# Debugger_1.net
KiCad netlist of a schematic drawn in EAGLE
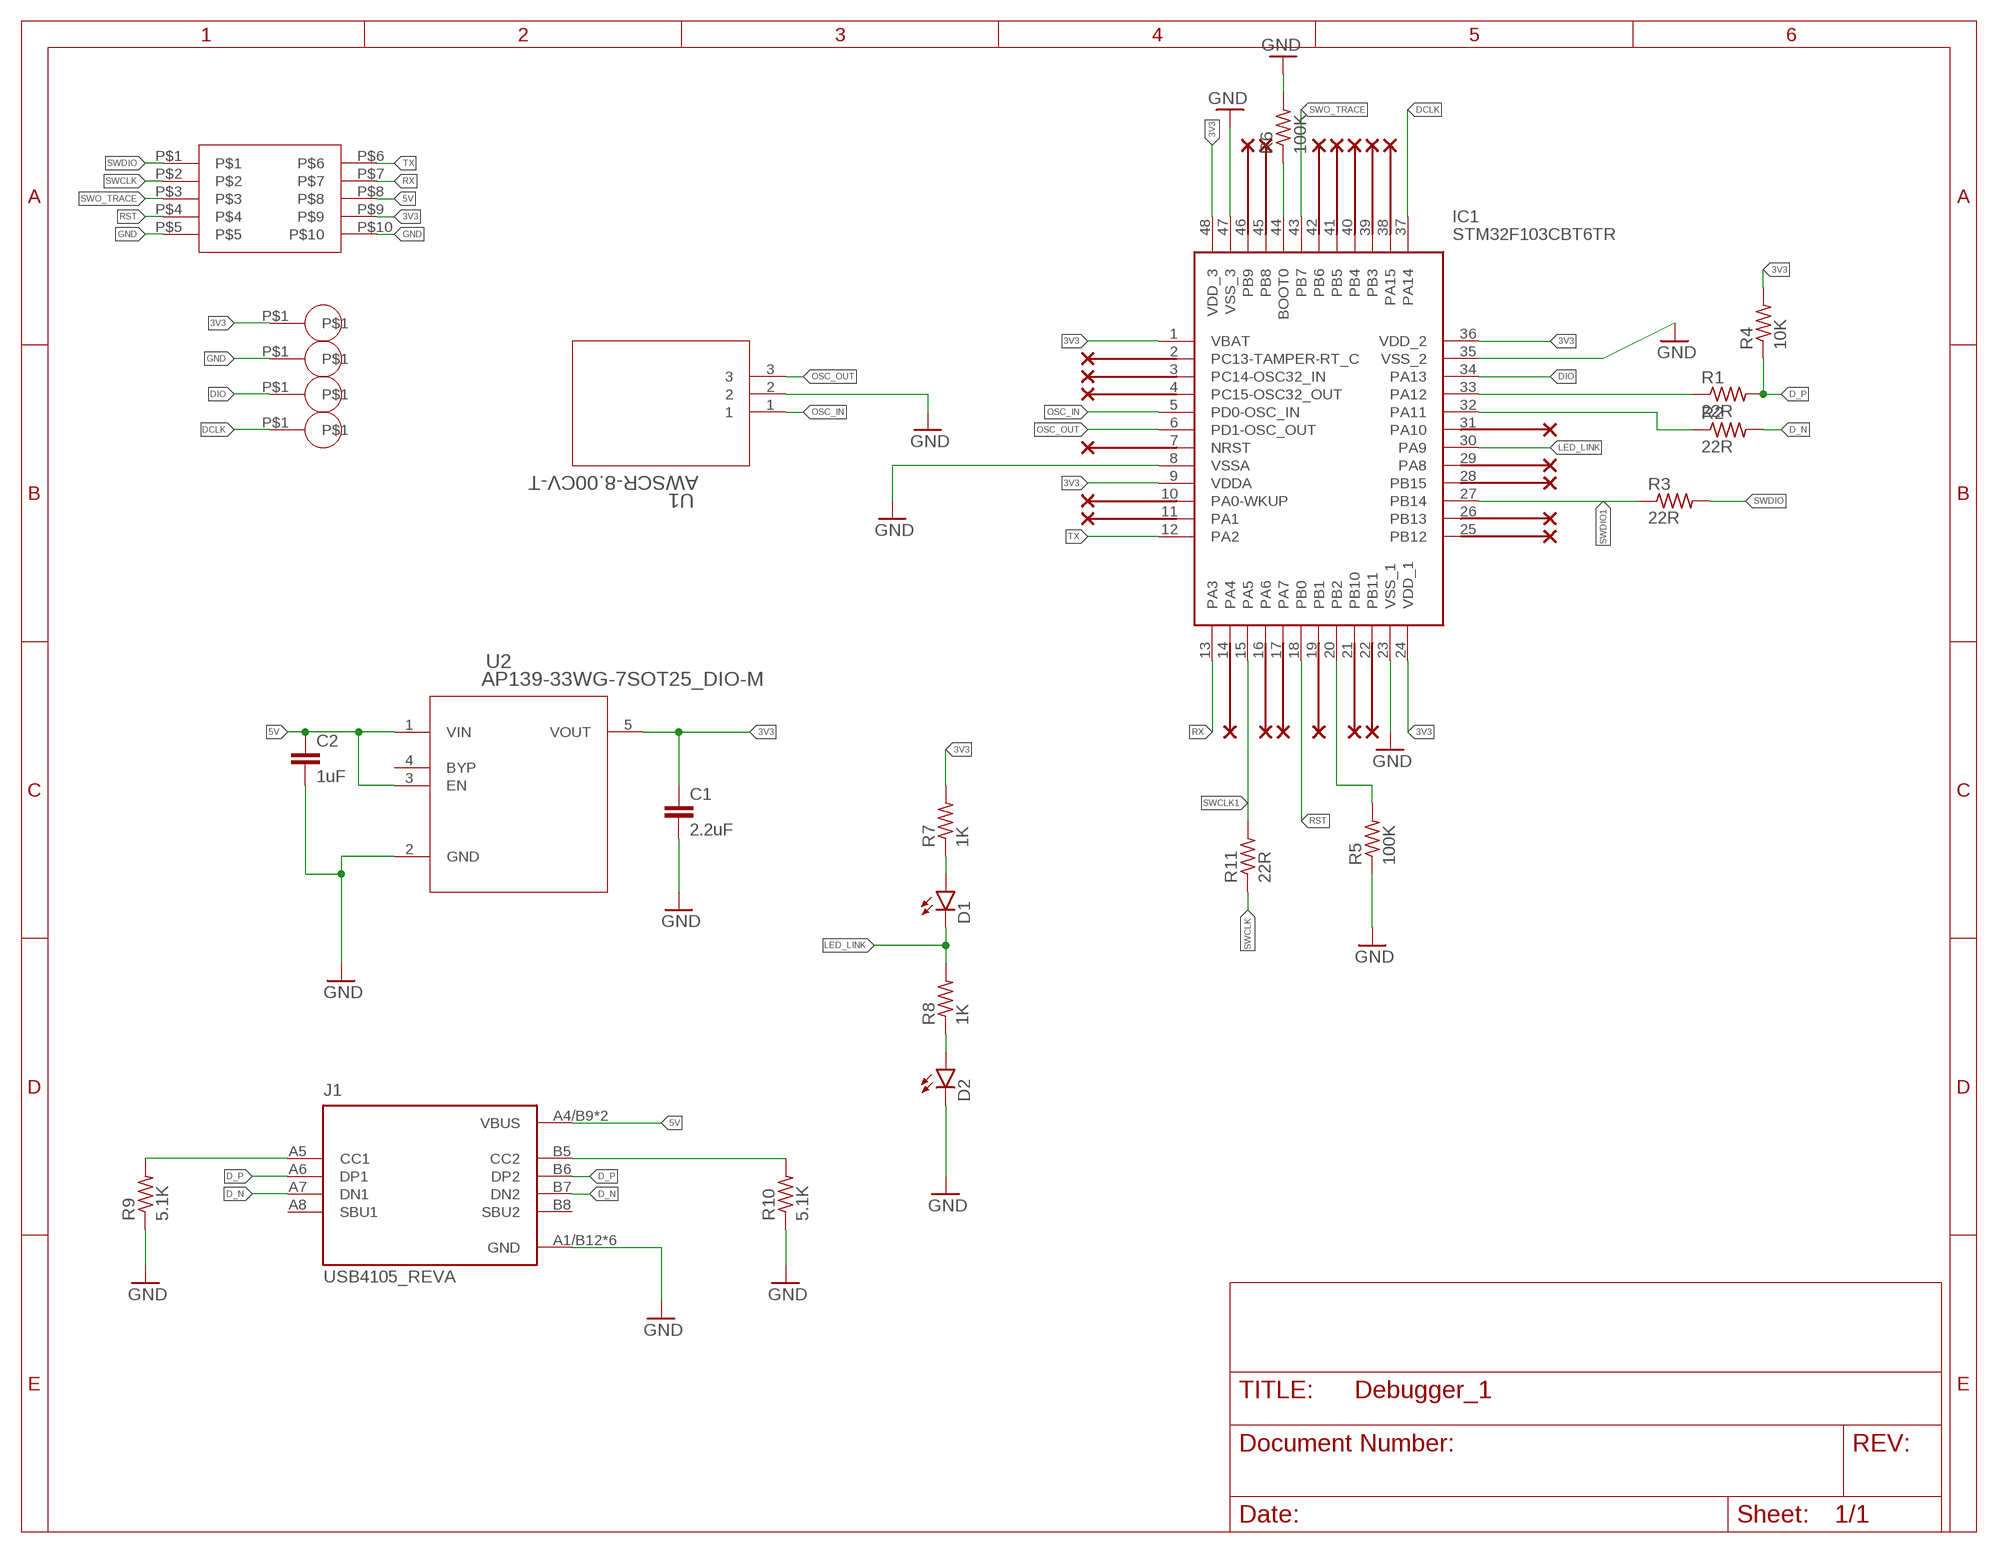
[diagram p0: schematic, sheet 1]

(export (version "E")
  (design (tool "Eeschema 10.0.6"))
  (components
    (comp (ref "C1")
      (value "2.2uF")
      (footprint "eagle-import:C0603")
      (libsource (lib "eagle-import") (part "C-EUC0603"))
    )
    (comp (ref "C2")
      (value "1uF")
      (footprint "eagle-import:C0603")
      (libsource (lib "eagle-import") (part "C-EUC0603"))
    )
    (comp (ref "D1")
      (value "LEDCHIPLED_0603")
      (footprint "eagle-import:CHIPLED_0603")
      (libsource (lib "eagle-import") (part "LEDCHIPLED_0603"))
    )
    (comp (ref "D2")
      (value "LEDCHIPLED_0603")
      (footprint "eagle-import:CHIPLED_0603")
      (libsource (lib "eagle-import") (part "LEDCHIPLED_0603"))
    )
    (comp (ref "IC1")
      (value "STM32F103CBT6TR")
      (footprint "eagle-import:QFP50P900X900X160-48N")
      (fields (field (name "MOUSER_PART_NUMBER") "511-STM32F103CBT6TR"))
      (libsource (lib "eagle-import") (part "STM32F103CBT6TR"))
    )
    (comp (ref "J1")
      (value "USB4105_REVA")
      (footprint "eagle-import:GCT_USB4105_REVA")
      (fields (field (name "MF") "Global Connector Technology") (field (name "MP") "USB4105"))
      (libsource (lib "eagle-import") (part "USB4105_REVA"))
    )
    (comp (ref "R1")
      (value "22R")
      (footprint "eagle-import:R0603")
      (libsource (lib "eagle-import") (part "R-US_R0603"))
    )
    (comp (ref "R2")
      (value "22R")
      (footprint "eagle-import:R0603")
      (libsource (lib "eagle-import") (part "R-US_R0603"))
    )
    (comp (ref "R3")
      (value "22R")
      (footprint "eagle-import:R0603")
      (libsource (lib "eagle-import") (part "R-US_R0603"))
    )
    (comp (ref "R4")
      (value "10K")
      (footprint "eagle-import:R0603")
      (libsource (lib "eagle-import") (part "R-US_R0603"))
    )
    (comp (ref "R5")
      (value "100K")
      (footprint "eagle-import:R0603")
      (libsource (lib "eagle-import") (part "R-US_R0603"))
    )
    (comp (ref "R6")
      (value "100K")
      (footprint "eagle-import:R0603")
      (libsource (lib "eagle-import") (part "R-US_R0603"))
    )
    (comp (ref "R7")
      (value "1K")
      (footprint "eagle-import:R0603")
      (libsource (lib "eagle-import") (part "R-US_R0603"))
    )
    (comp (ref "R8")
      (value "1K")
      (footprint "eagle-import:R0603")
      (libsource (lib "eagle-import") (part "R-US_R0603"))
    )
    (comp (ref "R9")
      (value "5.1K")
      (footprint "eagle-import:R0603")
      (libsource (lib "eagle-import") (part "R-US_R0603"))
    )
    (comp (ref "R10")
      (value "5.1K")
      (footprint "eagle-import:R0603")
      (libsource (lib "eagle-import") (part "R-US_R0603"))
    )
    (comp (ref "R11")
      (value "22R")
      (footprint "eagle-import:R0603")
      (libsource (lib "eagle-import") (part "R-US_R0603"))
    )
    (comp (ref "U$25")
      (value "SIDEWAYS_HEADER_10")
      (footprint "eagle-import:SIDEWAYS_HEADER_10")
      (libsource (lib "eagle-import") (part "SIDEWAYS_HEADER_10"))
    )
    (comp (ref "U$26")
      (value "SPRING_PAD_1")
      (footprint "eagle-import:SPRING_PAD_1")
      (libsource (lib "eagle-import") (part "SPRING_PAD_1"))
    )
    (comp (ref "U$27")
      (value "SPRING_PAD_1")
      (footprint "eagle-import:SPRING_PAD_1")
      (libsource (lib "eagle-import") (part "SPRING_PAD_1"))
    )
    (comp (ref "U$28")
      (value "SPRING_PAD_1")
      (footprint "eagle-import:SPRING_PAD_1")
      (libsource (lib "eagle-import") (part "SPRING_PAD_1"))
    )
    (comp (ref "U$29")
      (value "SPRING_PAD_1")
      (footprint "eagle-import:SPRING_PAD_1")
      (libsource (lib "eagle-import") (part "SPRING_PAD_1"))
    )
    (comp (ref "U1")
      (value "AWSCR-8.00CV-T")
      (footprint "eagle-import:AWSCR-8.00CV-T_ABR")
      (fields (field (name "COPYRIGHT") "Copyright (C) 2021 Ultra Librarian. All rights reserved."))
      (libsource (lib "eagle-import") (part "AWSCR-8.00CV-T"))
    )
    (comp (ref "U2")
      (value "AP139-33WG-7SOT25_DIO-M")
      (footprint "eagle-import:SOT25_DIO-M")
      (fields
        (field (name "MANUFACTURER_PART_NUMBER") "AP139-33WG-7")
        (field (name "COPYRIGHT") "Copyright (C) 2021 Ultra Librarian. All rights reserved.")
      )
      (libsource (lib "eagle-import") (part "AP139-33WG-7SOT25_DIO-M"))
    )
  )
  (nets
    (net (code "1") (name "3V3") (class "Default")
      (node (ref "C1") (pin "1") (pinfunction "1_1") (pintype "passive"))
      (node (ref "IC1") (pin "1") (pinfunction "VBAT_1") (pintype "bidirectional"))
      (node (ref "IC1") (pin "24") (pinfunction "VDD_1_24") (pintype "bidirectional"))
      (node (ref "IC1") (pin "36") (pinfunction "VDD_2_36") (pintype "bidirectional"))
      (node (ref "IC1") (pin "48") (pinfunction "VDD_3_48") (pintype "bidirectional"))
      (node (ref "IC1") (pin "9") (pinfunction "VDDA_9") (pintype "bidirectional"))
      (node (ref "R4") (pin "2") (pinfunction "2_2") (pintype "passive"))
      (node (ref "R7") (pin "2") (pinfunction "2_2") (pintype "passive"))
      (node (ref "U$25") (pin "P$9") (pinfunction "P$9_P$9") (pintype "bidirectional"))
      (node (ref "U$26") (pin "P$1") (pinfunction "P$1_P$1") (pintype "bidirectional"))
      (node (ref "U2") (pin "5") (pinfunction "VOUT_5") (pintype "output"))
    )
    (net (code "2") (name "5V") (class "Default")
      (node (ref "C2") (pin "1") (pinfunction "1_1") (pintype "passive"))
      (node (ref "J1") (pin "A4/B9") (pinfunction "VBUS_A4/B9") (pintype "power_in"))
      (node (ref "J1") (pin "B4/A9") (pinfunction "VBUS_B4/A9") (pintype "power_in"))
      (node (ref "U$25") (pin "P$8") (pinfunction "P$8_P$8") (pintype "bidirectional"))
      (node (ref "U2") (pin "1") (pinfunction "VIN_1") (pintype "input"))
      (node (ref "U2") (pin "3") (pinfunction "EN_3") (pintype "passive"))
    )
    (net (code "3") (name "DCLK") (class "Default")
      (node (ref "IC1") (pin "37") (pinfunction "PA14_37") (pintype "bidirectional"))
      (node (ref "U$29") (pin "P$1") (pinfunction "P$1_P$1") (pintype "bidirectional"))
    )
    (net (code "4") (name "DIO") (class "Default")
      (node (ref "IC1") (pin "34") (pinfunction "PA13_34") (pintype "bidirectional"))
      (node (ref "U$28") (pin "P$1") (pinfunction "P$1_P$1") (pintype "bidirectional"))
    )
    (net (code "5") (name "D_N") (class "Default")
      (node (ref "J1") (pin "A7") (pinfunction "DN1_A7") (pintype "bidirectional"))
      (node (ref "J1") (pin "B7") (pinfunction "DN2_B7") (pintype "bidirectional"))
      (node (ref "R2") (pin "2") (pinfunction "2_2") (pintype "passive"))
    )
    (net (code "6") (name "D_P") (class "Default")
      (node (ref "J1") (pin "A6") (pinfunction "DP1_A6") (pintype "bidirectional"))
      (node (ref "J1") (pin "B6") (pinfunction "DP2_B6") (pintype "bidirectional"))
      (node (ref "R1") (pin "2") (pinfunction "2_2") (pintype "passive"))
      (node (ref "R4") (pin "1") (pinfunction "1_1") (pintype "passive"))
    )
    (net (code "7") (name "GND") (class "Default")
      (node (ref "C1") (pin "2") (pinfunction "2_2") (pintype "passive"))
      (node (ref "C2") (pin "2") (pinfunction "2_2") (pintype "passive"))
      (node (ref "D2") (pin "C") (pinfunction "C_C") (pintype "passive"))
      (node (ref "IC1") (pin "23") (pinfunction "VSS_1_23") (pintype "bidirectional"))
      (node (ref "IC1") (pin "35") (pinfunction "VSS_2_35") (pintype "bidirectional"))
      (node (ref "IC1") (pin "47") (pinfunction "VSS_3_47") (pintype "bidirectional"))
      (node (ref "IC1") (pin "8") (pinfunction "VSSA_8") (pintype "bidirectional"))
      (node (ref "J1") (pin "A1/B12") (pinfunction "GND_A1/B12") (pintype "power_in"))
      (node (ref "J1") (pin "B1/A12") (pinfunction "GND_B1/A12") (pintype "power_in"))
      (node (ref "J1") (pin "G1") (pinfunction "GND_G1") (pintype "power_in"))
      (node (ref "J1") (pin "G2") (pinfunction "GND_G2") (pintype "power_in"))
      (node (ref "J1") (pin "G3") (pinfunction "GND_G3") (pintype "power_in"))
      (node (ref "J1") (pin "G4") (pinfunction "GND_G4") (pintype "power_in"))
      (node (ref "R10") (pin "1") (pinfunction "1_1") (pintype "passive"))
      (node (ref "R5") (pin "1") (pinfunction "1_1") (pintype "passive"))
      (node (ref "R6") (pin "2") (pinfunction "2_2") (pintype "passive"))
      (node (ref "R9") (pin "1") (pinfunction "1_1") (pintype "passive"))
      (node (ref "U$25") (pin "P$10") (pinfunction "P$10_P$10") (pintype "bidirectional"))
      (node (ref "U$25") (pin "P$5") (pinfunction "P$5_P$5") (pintype "bidirectional"))
      (node (ref "U$27") (pin "P$1") (pinfunction "P$1_P$1") (pintype "bidirectional"))
      (node (ref "U1") (pin "2") (pinfunction "2_2") (pintype "passive"))
      (node (ref "U2") (pin "2") (pinfunction "GND_2") (pintype "power_in"))
    )
    (net (code "8") (name "LED_LINK") (class "Default")
      (node (ref "D1") (pin "C") (pinfunction "C_C") (pintype "passive"))
      (node (ref "IC1") (pin "30") (pinfunction "PA9_30") (pintype "bidirectional"))
      (node (ref "R8") (pin "2") (pinfunction "2_2") (pintype "passive"))
    )
    (net (code "9") (name "Net-(D1-PadA)") (class "Default")
      (node (ref "D1") (pin "A") (pinfunction "A_A") (pintype "passive"))
      (node (ref "R7") (pin "1") (pinfunction "1_1") (pintype "passive"))
    )
    (net (code "10") (name "Net-(D2-PadA)") (class "Default")
      (node (ref "D2") (pin "A") (pinfunction "A_A") (pintype "passive"))
      (node (ref "R8") (pin "1") (pinfunction "1_1") (pintype "passive"))
    )
    (net (code "11") (name "Net-(IC1-BOOT0)") (class "Default")
      (node (ref "IC1") (pin "44") (pinfunction "BOOT0_44") (pintype "bidirectional"))
      (node (ref "R6") (pin "1") (pinfunction "1_1") (pintype "passive"))
    )
    (net (code "12") (name "Net-(IC1-PA11)") (class "Default")
      (node (ref "IC1") (pin "32") (pinfunction "PA11_32") (pintype "bidirectional"))
      (node (ref "R2") (pin "1") (pinfunction "1_1") (pintype "passive"))
    )
    (net (code "13") (name "Net-(IC1-PA12)") (class "Default")
      (node (ref "IC1") (pin "33") (pinfunction "PA12_33") (pintype "bidirectional"))
      (node (ref "R1") (pin "1") (pinfunction "1_1") (pintype "passive"))
    )
    (net (code "14") (name "Net-(IC1-PB2)") (class "Default")
      (node (ref "IC1") (pin "20") (pinfunction "PB2_20") (pintype "bidirectional"))
      (node (ref "R5") (pin "2") (pinfunction "2_2") (pintype "passive"))
    )
    (net (code "15") (name "Net-(J1-CC1)") (class "Default")
      (node (ref "J1") (pin "A5") (pinfunction "CC1_A5") (pintype "bidirectional"))
      (node (ref "R9") (pin "2") (pinfunction "2_2") (pintype "passive"))
    )
    (net (code "16") (name "Net-(J1-CC2)") (class "Default")
      (node (ref "J1") (pin "B5") (pinfunction "CC2_B5") (pintype "bidirectional"))
      (node (ref "R10") (pin "2") (pinfunction "2_2") (pintype "passive"))
    )
    (net (code "17") (name "OSC_IN") (class "Default")
      (node (ref "IC1") (pin "5") (pinfunction "PD0-OSC_IN_5") (pintype "bidirectional"))
      (node (ref "U1") (pin "1") (pinfunction "1_1") (pintype "passive"))
    )
    (net (code "18") (name "OSC_OUT") (class "Default")
      (node (ref "IC1") (pin "6") (pinfunction "PD1-OSC_OUT_6") (pintype "bidirectional"))
      (node (ref "U1") (pin "3") (pinfunction "3_3") (pintype "passive"))
    )
    (net (code "19") (name "RST") (class "Default")
      (node (ref "IC1") (pin "18") (pinfunction "PB0_18") (pintype "bidirectional"))
      (node (ref "U$25") (pin "P$4") (pinfunction "P$4_P$4") (pintype "bidirectional"))
    )
    (net (code "20") (name "RX") (class "Default")
      (node (ref "IC1") (pin "13") (pinfunction "PA3_13") (pintype "bidirectional"))
      (node (ref "U$25") (pin "P$7") (pinfunction "P$7_P$7") (pintype "bidirectional"))
    )
    (net (code "21") (name "SWCLK") (class "Default")
      (node (ref "R11") (pin "1") (pinfunction "1_1") (pintype "passive"))
      (node (ref "U$25") (pin "P$2") (pinfunction "P$2_P$2") (pintype "bidirectional"))
    )
    (net (code "22") (name "SWCLK1") (class "Default")
      (node (ref "IC1") (pin "15") (pinfunction "PA5_15") (pintype "bidirectional"))
      (node (ref "R11") (pin "2") (pinfunction "2_2") (pintype "passive"))
    )
    (net (code "23") (name "SWDIO") (class "Default")
      (node (ref "R3") (pin "2") (pinfunction "2_2") (pintype "passive"))
      (node (ref "U$25") (pin "P$1") (pinfunction "P$1_P$1") (pintype "bidirectional"))
    )
    (net (code "24") (name "SWDIO1") (class "Default")
      (node (ref "IC1") (pin "27") (pinfunction "PB14_27") (pintype "bidirectional"))
      (node (ref "R3") (pin "1") (pinfunction "1_1") (pintype "passive"))
    )
    (net (code "25") (name "SWO_TRACE") (class "Default")
      (node (ref "IC1") (pin "43") (pinfunction "PB7_43") (pintype "bidirectional"))
      (node (ref "U$25") (pin "P$3") (pinfunction "P$3_P$3") (pintype "bidirectional"))
    )
    (net (code "26") (name "TX") (class "Default")
      (node (ref "IC1") (pin "12") (pinfunction "PA2_12") (pintype "bidirectional"))
      (node (ref "U$25") (pin "P$6") (pinfunction "P$6_P$6") (pintype "bidirectional"))
    )
    (net (code "27") (name "unconnected-(IC1-NRST-Pad7)") (class "Default")
      (node (ref "IC1") (pin "7") (pinfunction "NRST_7") (pintype "bidirectional"))
    )
    (net (code "28") (name "unconnected-(IC1-PA0-WKUP-Pad10)") (class "Default")
      (node (ref "IC1") (pin "10") (pinfunction "PA0-WKUP_10") (pintype "bidirectional"))
    )
    (net (code "29") (name "unconnected-(IC1-PA1-Pad11)") (class "Default")
      (node (ref "IC1") (pin "11") (pinfunction "PA1_11") (pintype "bidirectional"))
    )
    (net (code "30") (name "unconnected-(IC1-PA4-Pad14)") (class "Default")
      (node (ref "IC1") (pin "14") (pinfunction "PA4_14") (pintype "bidirectional"))
    )
    (net (code "31") (name "unconnected-(IC1-PA6-Pad16)") (class "Default")
      (node (ref "IC1") (pin "16") (pinfunction "PA6_16") (pintype "bidirectional"))
    )
    (net (code "32") (name "unconnected-(IC1-PA7-Pad17)") (class "Default")
      (node (ref "IC1") (pin "17") (pinfunction "PA7_17") (pintype "bidirectional"))
    )
    (net (code "33") (name "unconnected-(IC1-PA8-Pad29)") (class "Default")
      (node (ref "IC1") (pin "29") (pinfunction "PA8_29") (pintype "bidirectional"))
    )
    (net (code "34") (name "unconnected-(IC1-PA10-Pad31)") (class "Default")
      (node (ref "IC1") (pin "31") (pinfunction "PA10_31") (pintype "bidirectional"))
    )
    (net (code "35") (name "unconnected-(IC1-PA15-Pad38)") (class "Default")
      (node (ref "IC1") (pin "38") (pinfunction "PA15_38") (pintype "bidirectional"))
    )
    (net (code "36") (name "unconnected-(IC1-PB1-Pad19)") (class "Default")
      (node (ref "IC1") (pin "19") (pinfunction "PB1_19") (pintype "bidirectional"))
    )
    (net (code "37") (name "unconnected-(IC1-PB3-Pad39)") (class "Default")
      (node (ref "IC1") (pin "39") (pinfunction "PB3_39") (pintype "bidirectional"))
    )
    (net (code "38") (name "unconnected-(IC1-PB4-Pad40)") (class "Default")
      (node (ref "IC1") (pin "40") (pinfunction "PB4_40") (pintype "bidirectional"))
    )
    (net (code "39") (name "unconnected-(IC1-PB5-Pad41)") (class "Default")
      (node (ref "IC1") (pin "41") (pinfunction "PB5_41") (pintype "bidirectional"))
    )
    (net (code "40") (name "unconnected-(IC1-PB6-Pad42)") (class "Default")
      (node (ref "IC1") (pin "42") (pinfunction "PB6_42") (pintype "bidirectional"))
    )
    (net (code "41") (name "unconnected-(IC1-PB8-Pad45)") (class "Default")
      (node (ref "IC1") (pin "45") (pinfunction "PB8_45") (pintype "bidirectional"))
    )
    (net (code "42") (name "unconnected-(IC1-PB9-Pad46)") (class "Default")
      (node (ref "IC1") (pin "46") (pinfunction "PB9_46") (pintype "bidirectional"))
    )
    (net (code "43") (name "unconnected-(IC1-PB10-Pad21)") (class "Default")
      (node (ref "IC1") (pin "21") (pinfunction "PB10_21") (pintype "bidirectional"))
    )
    (net (code "44") (name "unconnected-(IC1-PB11-Pad22)") (class "Default")
      (node (ref "IC1") (pin "22") (pinfunction "PB11_22") (pintype "bidirectional"))
    )
    (net (code "45") (name "unconnected-(IC1-PB12-Pad25)") (class "Default")
      (node (ref "IC1") (pin "25") (pinfunction "PB12_25") (pintype "bidirectional"))
    )
    (net (code "46") (name "unconnected-(IC1-PB13-Pad26)") (class "Default")
      (node (ref "IC1") (pin "26") (pinfunction "PB13_26") (pintype "bidirectional"))
    )
    (net (code "47") (name "unconnected-(IC1-PB15-Pad28)") (class "Default")
      (node (ref "IC1") (pin "28") (pinfunction "PB15_28") (pintype "bidirectional"))
    )
    (net (code "48") (name "unconnected-(IC1-PC13-TAMPER-RT_C-Pad2)") (class "Default")
      (node (ref "IC1") (pin "2") (pinfunction "PC13-TAMPER-RT_C_2") (pintype "bidirectional"))
    )
    (net (code "49") (name "unconnected-(IC1-PC14-OSC32_IN-Pad3)") (class "Default")
      (node (ref "IC1") (pin "3") (pinfunction "PC14-OSC32_IN_3") (pintype "bidirectional"))
    )
    (net (code "50") (name "unconnected-(IC1-PC15-OSC32_OUT-Pad4)") (class "Default")
      (node (ref "IC1") (pin "4") (pinfunction "PC15-OSC32_OUT_4") (pintype "bidirectional"))
    )
    (net (code "51") (name "unconnected-(J1-SBU1-PadA8)") (class "Default")
      (node (ref "J1") (pin "A8") (pinfunction "SBU1_A8") (pintype "bidirectional"))
    )
    (net (code "52") (name "unconnected-(J1-SBU2-PadB8)") (class "Default")
      (node (ref "J1") (pin "B8") (pinfunction "SBU2_B8") (pintype "bidirectional"))
    )
    (net (code "53") (name "unconnected-(U2-BYP-Pad4)") (class "Default")
      (node (ref "U2") (pin "4") (pinfunction "BYP_4") (pintype "passive"))
    )
  )
)
